# 2024_LV_BMS.net
KiCad netlist of a schematic drawn in Altium Designer
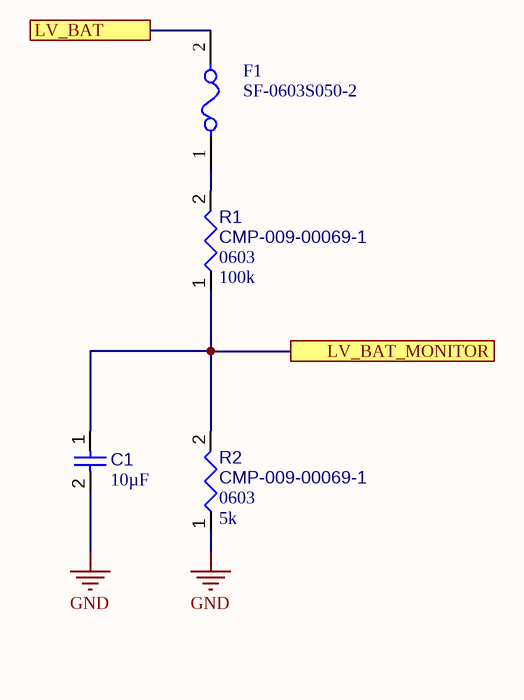
[diagram p0: 2024 LV BMS.SchDoc]

(export (version "E")
  (design (tool "Eeschema 10.0.6"))
  (components
    (comp (ref "C1")
      (value "10µF")
      (footprint "CAPC0603(1608)100_L")
      (description "Chip Capacitor, 10 uF, +/- 10%, 16 V, 1206 (3216 Metric)")
      (fields
        (field (name "TOLERANCE") "10%")
        (field (name "Comment") "CMP-001-00016-4")
        (field (name "AVAILABLE PREVIEW IMAGES") "2D")
      )
      (libsource (lib "") (part "Symbol_1"))
    )
    (comp (ref "F1")
      (value "SF-0603S050-2")
      (footprint "FP-SF-0603S-MFG")
      (description "500mA AC 50V DC Fuse Board Mount (Cartridge Style Excluded) Surface Mount 0603 (1608 Metric)")
      (fields (field (name "MANUFACTURER") "Bourns Inc."))
      (libsource (lib "Altium Content Vault") (part "5bcf9b9f640e542cf0359d10258e979"))
    )
    (comp (ref "R1")
      (value "CMP-009-00069-1")
      (footprint "RESC0603(1608)_L")
      (description "120R 0.1W 5% 0603 (1608 Metric)  SMD")
      (fields
        (field (name "CASE/PACKAGE") "0603")
        (field (name "ALTIUM_VALUE") "100k")
        (field (name "AVAILABLE PREVIEW IMAGES") "2D")
      )
      (libsource (lib "Illini Formula Electric") (part "Symbol"))
    )
    (comp (ref "R2")
      (value "CMP-009-00069-1")
      (footprint "RESC0603(1608)_L")
      (description "120R 0.1W 5% 0603 (1608 Metric)  SMD")
      (fields
        (field (name "CASE/PACKAGE") "0603")
        (field (name "ALTIUM_VALUE") "5k")
        (field (name "AVAILABLE PREVIEW IMAGES") "2D")
      )
      (libsource (lib "Illini Formula Electric") (part "Symbol"))
    )
  )
  (nets
    (net (code "1") (name "/LV_BAT") (class "Default")
      (node (ref "F1") (pin "2") (pinfunction "2_2") (pintype "passive"))
    )
    (net (code "2") (name "/LV_BAT_MONITOR") (class "Default")
      (node (ref "C1") (pin "1") (pinfunction "1_1") (pintype "passive"))
      (node (ref "R1") (pin "1") (pinfunction "1_1") (pintype "passive"))
      (node (ref "R2") (pin "2") (pinfunction "2_2") (pintype "passive"))
    )
    (net (code "3") (name "GND") (class "Default")
      (node (ref "C1") (pin "2") (pinfunction "2_2") (pintype "passive"))
      (node (ref "R2") (pin "1") (pinfunction "1_1") (pintype "passive"))
    )
    (net (code "4") (name "Net-(F1-Pad1)") (class "Default")
      (node (ref "F1") (pin "1") (pinfunction "1_1") (pintype "passive"))
      (node (ref "R1") (pin "2") (pinfunction "2_2") (pintype "passive"))
    )
  )
)
